# Splitter.net
KiCad netlist of a schematic drawn in Altium Designer
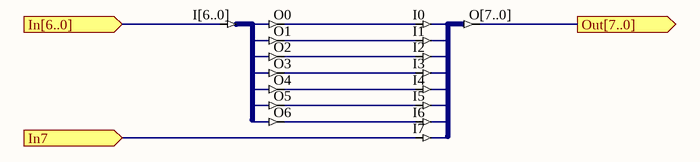
[diagram p0: Splitter.SchDoc]

(export (version "E")
  (design (tool "Eeschema 10.0.6"))
  (components
    (comp (ref "U110")
      (value "J8S_8B")
      (description "8 Single pin inputs to single 8-Bit output bus")
      (fields (field (name "PUBLISHER") "Altium Limited"))
      (libsource (lib "FPGA Generic") (part "J8S_8B"))
    )
    (comp (ref "U116")
      (value "J7B_7S")
      (description "7-Bit input bus to 7 Single pin outputs")
      (fields (field (name "PUBLISHER") "Altium Limited"))
      (libsource (lib "FPGA Generic") (part "J7B_7S"))
    )
  )
  (nets
    (net (code "16") (name "/In7") (class "Default")
      (node (ref "U110") (pin "I7") (pinfunction "I7_I7") (pintype "input"))
    )
    (net (code "17") (name "/In[6..0]") (class "Default")
      (node (ref "U116") (pin "I[6..0]") (pinfunction "I[6..0]_I[6..0]") (pintype "input"))
    )
    (net (code "18") (name "/Out[7..0]") (class "Default")
      (node (ref "U110") (pin "O[7..0]") (pinfunction "O[7..0]_O[7..0]") (pintype "output"))
    )
    (net (code "19") (name "Net-(U110-PadI0)") (class "Default")
      (node (ref "U110") (pin "I0") (pinfunction "I0_I0") (pintype "input"))
      (node (ref "U116") (pin "O0") (pinfunction "O0_O0") (pintype "output"))
    )
    (net (code "20") (name "Net-(U110-PadI1)") (class "Default")
      (node (ref "U110") (pin "I1") (pinfunction "I1_I1") (pintype "input"))
      (node (ref "U116") (pin "O1") (pinfunction "O1_O1") (pintype "output"))
    )
    (net (code "21") (name "Net-(U110-PadI2)") (class "Default")
      (node (ref "U110") (pin "I2") (pinfunction "I2_I2") (pintype "input"))
      (node (ref "U116") (pin "O2") (pinfunction "O2_O2") (pintype "output"))
    )
    (net (code "22") (name "Net-(U110-PadI3)") (class "Default")
      (node (ref "U110") (pin "I3") (pinfunction "I3_I3") (pintype "input"))
      (node (ref "U116") (pin "O3") (pinfunction "O3_O3") (pintype "output"))
    )
    (net (code "23") (name "Net-(U110-PadI4)") (class "Default")
      (node (ref "U110") (pin "I4") (pinfunction "I4_I4") (pintype "input"))
      (node (ref "U116") (pin "O4") (pinfunction "O4_O4") (pintype "output"))
    )
    (net (code "24") (name "Net-(U110-PadI5)") (class "Default")
      (node (ref "U110") (pin "I5") (pinfunction "I5_I5") (pintype "input"))
      (node (ref "U116") (pin "O5") (pinfunction "O5_O5") (pintype "output"))
    )
    (net (code "25") (name "Net-(U110-PadI6)") (class "Default")
      (node (ref "U110") (pin "I6") (pinfunction "I6_I6") (pintype "input"))
      (node (ref "U116") (pin "O6") (pinfunction "O6_O6") (pintype "output"))
    )
  )
)
